# CAN.net
KiCad netlist of a schematic drawn in Altium Designer
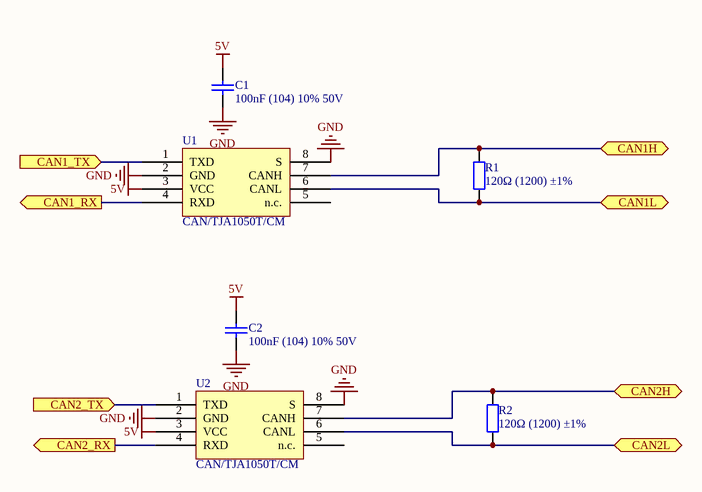
[diagram p0: CAN.SchDoc]

(export (version "E")
  (design (tool "Eeschema 10.0.6"))
  (components
    (comp (ref "C1")
      (value "100nF (104) 10% 50V")
      (footprint "0603_C")
      (description "贴片电容")
      (libsource (lib "Miscellaneous Devices LC") (part "0603 100nF (104) 10% 50V"))
    )
    (comp (ref "C2")
      (value "100nF (104) 10% 50V")
      (footprint "0603_C")
      (description "贴片电容")
      (libsource (lib "Miscellaneous Devices LC") (part "0603 100nF (104) 10% 50V"))
    )
    (comp (ref "R1")
      (value "120Ω (1200) ±1%")
      (footprint "0603_R")
      (description "贴片电阻")
      (libsource (lib "Miscellaneous Devices LC") (part "0603 120Ω (1200) 1%"))
    )
    (comp (ref "R2")
      (value "120Ω (1200) ±1%")
      (footprint "0603_R")
      (description "贴片电阻")
      (libsource (lib "Miscellaneous Devices LC") (part "0603 120Ω (1200) 1%"))
    )
    (comp (ref "U1")
      (value "CAN/TJA1050T/CM")
      (footprint "SOIC-8_150mil")
      (description "CAN")
      (libsource (lib "Miscellaneous Devices LC") (part "CAN/TJA1050T/CM_[C6952]"))
    )
    (comp (ref "U2")
      (value "CAN/TJA1050T/CM")
      (footprint "SOIC-8_150mil")
      (description "CAN")
      (libsource (lib "Miscellaneous Devices LC") (part "CAN/TJA1050T/CM_[C6952]"))
    )
  )
  (nets
    (net (code "1") (name "/CAN1H") (class "Default")
      (node (ref "R1") (pin "2") (pinfunction "2_2") (pintype "passive"))
      (node (ref "U1") (pin "7") (pinfunction "CANH_7") (pintype "passive"))
    )
    (net (code "2") (name "/CAN1L") (class "Default")
      (node (ref "R1") (pin "1") (pinfunction "1_1") (pintype "passive"))
      (node (ref "U1") (pin "6") (pinfunction "CANL_6") (pintype "passive"))
    )
    (net (code "3") (name "/CAN1_RX") (class "Default")
      (node (ref "U1") (pin "4") (pinfunction "RXD_4") (pintype "passive"))
    )
    (net (code "4") (name "/CAN1_TX") (class "Default")
      (node (ref "U1") (pin "1") (pinfunction "TXD_1") (pintype "passive"))
    )
    (net (code "5") (name "/CAN2H") (class "Default")
      (node (ref "R2") (pin "2") (pinfunction "2_2") (pintype "passive"))
      (node (ref "U2") (pin "7") (pinfunction "CANH_7") (pintype "passive"))
    )
    (net (code "6") (name "/CAN2L") (class "Default")
      (node (ref "R2") (pin "1") (pinfunction "1_1") (pintype "passive"))
      (node (ref "U2") (pin "6") (pinfunction "CANL_6") (pintype "passive"))
    )
    (net (code "7") (name "/CAN2_RX") (class "Default")
      (node (ref "U2") (pin "4") (pinfunction "RXD_4") (pintype "passive"))
    )
    (net (code "8") (name "/CAN2_TX") (class "Default")
      (node (ref "U2") (pin "1") (pinfunction "TXD_1") (pintype "passive"))
    )
    (net (code "9") (name "5V") (class "Default")
      (node (ref "C1") (pin "2") (pinfunction "2_2") (pintype "passive"))
      (node (ref "C2") (pin "2") (pinfunction "2_2") (pintype "passive"))
      (node (ref "U1") (pin "3") (pinfunction "VCC_3") (pintype "passive"))
      (node (ref "U2") (pin "3") (pinfunction "VCC_3") (pintype "passive"))
    )
    (net (code "10") (name "GND") (class "Default")
      (node (ref "C1") (pin "1") (pinfunction "1_1") (pintype "passive"))
      (node (ref "C2") (pin "1") (pinfunction "1_1") (pintype "passive"))
      (node (ref "U1") (pin "2") (pinfunction "GND_2") (pintype "passive"))
      (node (ref "U1") (pin "8") (pinfunction "S_8") (pintype "passive"))
      (node (ref "U2") (pin "2") (pinfunction "GND_2") (pintype "passive"))
      (node (ref "U2") (pin "8") (pinfunction "S_8") (pintype "passive"))
    )
    (net (code "11") (name "unconnected-(U1-n.c.-Pad5)") (class "Default")
      (node (ref "U1") (pin "5") (pinfunction "n.c._5") (pintype "passive"))
    )
    (net (code "12") (name "unconnected-(U2-n.c.-Pad5)") (class "Default")
      (node (ref "U2") (pin "5") (pinfunction "n.c._5") (pintype "passive"))
    )
  )
)
